# can-transceiver.net
KiCad netlist of a schematic drawn in Altium Designer
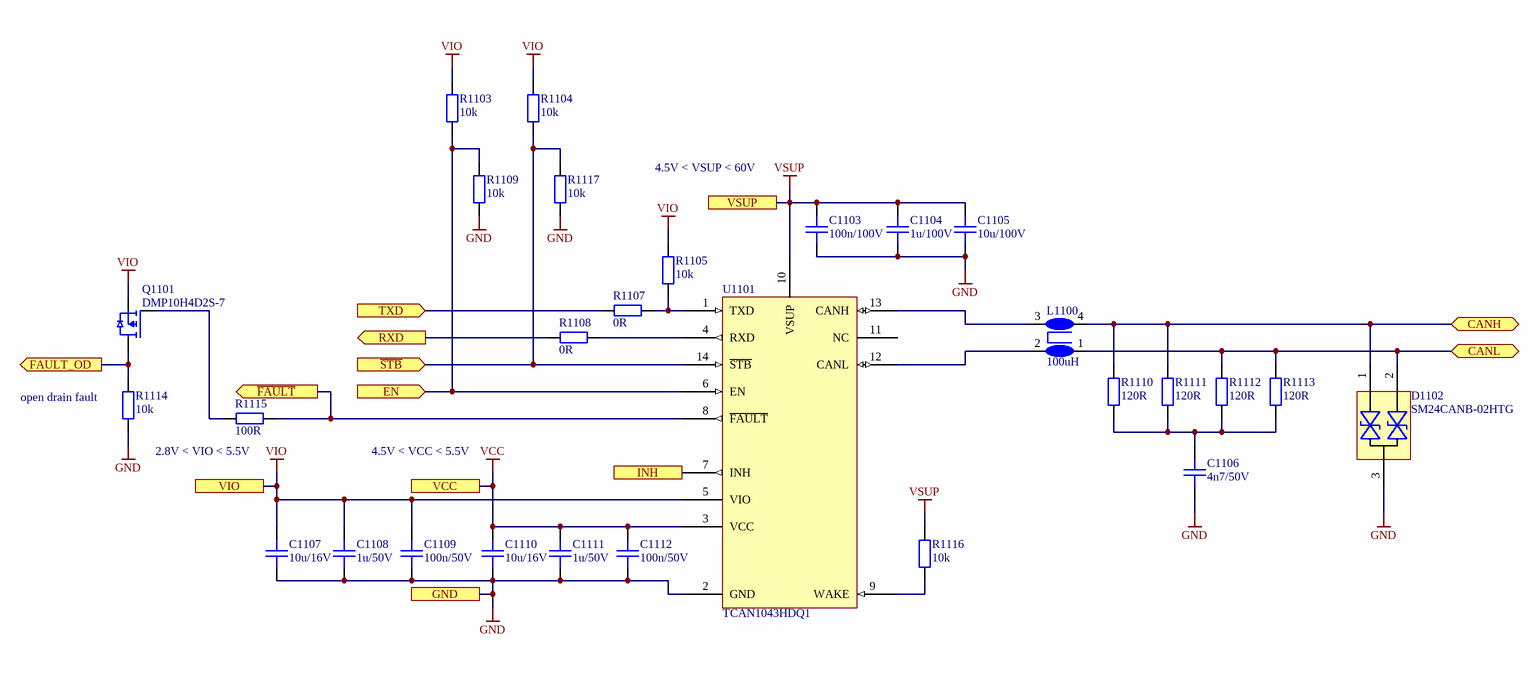
[diagram p0: can-transceiver.SchDoc]

(export (version "E")
  (design (tool "Eeschema 10.0.6"))
  (components
    (comp (ref "C1103")
      (value "100n/100V")
      (footprint "CAPC1608X08N")
      (description "MLCC")
      (fields (field (name "PART NUMBER") "gen_C_ceramic_100n_100V_X7R_0603"))
      (libsource (lib "OE750") (part "C"))
    )
    (comp (ref "C1104")
      (value "1u/100V")
      (footprint "CAPC3216X18N")
      (description "MLCC")
      (fields (field (name "PART NUMBER") "gen_C_ceramic_1u_100V_X7R_1206"))
      (libsource (lib "OE750") (part "C"))
    )
    (comp (ref "C1105")
      (value "10u/100V")
      (footprint "CAPC5750X28N")
      (description "MLCC")
      (fields (field (name "PART NUMBER") "gen_C_ceramic_10u_100V_X7S_2220"))
      (libsource (lib "OE750") (part "C"))
    )
    (comp (ref "C1106")
      (value "4n7/50V")
      (footprint "CAPC1005X06N")
      (description "MLCC")
      (fields (field (name "PART NUMBER") "gen_C_ceramic_4n7_50V_X7R_0402"))
      (libsource (lib "OE750") (part "C"))
    )
    (comp (ref "C1107")
      (value "10u/16V")
      (footprint "CAPC2012X14N")
      (description "MLCC")
      (fields (field (name "PART NUMBER") "gen_C_ceramic_10u_16V_X7R_0805"))
      (libsource (lib "OE750") (part "C"))
    )
    (comp (ref "C1108")
      (value "1u/50V")
      (footprint "CAPC1608X08N")
      (description "MLCC")
      (fields (field (name "PART NUMBER") "gen_C_ceramic_1u_50V_X7R_0603") (field (name "TOLERANCE") "± 10%"))
      (libsource (lib "OE750") (part "C"))
    )
    (comp (ref "C1109")
      (value "100n/50V")
      (footprint "CAPC1005X06N")
      (description "MLCC")
      (fields (field (name "PART NUMBER") "gen_C_ceramic_100n_50V_X7R_0402"))
      (libsource (lib "OE750") (part "C"))
    )
    (comp (ref "C1110")
      (value "10u/16V")
      (footprint "CAPC2012X14N")
      (description "MLCC")
      (fields (field (name "PART NUMBER") "gen_C_ceramic_10u_16V_X7R_0805"))
      (libsource (lib "OE750") (part "C"))
    )
    (comp (ref "C1111")
      (value "1u/50V")
      (footprint "CAPC1608X08N")
      (description "MLCC")
      (fields (field (name "PART NUMBER") "gen_C_ceramic_1u_50V_X7R_0603") (field (name "TOLERANCE") "± 10%"))
      (libsource (lib "OE750") (part "C"))
    )
    (comp (ref "C1112")
      (value "100n/50V")
      (footprint "CAPC1005X06N")
      (description "MLCC")
      (fields (field (name "PART NUMBER") "gen_C_ceramic_100n_50V_X7R_0402"))
      (libsource (lib "OE750") (part "C"))
    )
    (comp (ref "D1102")
      (value "SM24CANB-02HTG")
      (footprint "LF_SOT23-3")
      (description "CAN ESD Protection Diode Array")
      (fields (field (name "MANUFACTURER") "Littelfuse"))
      (libsource (lib "OE750") (part "SM24CANB"))
    )
    (comp (ref "L1100")
      (value "100uH")
      (footprint "MURATA_DLW32SH")
      (description "Common Mode Choke")
      (fields (field (name "PART NUMBER") "DLW32SH101XF2L") (field (name "MANUFACTURER") "Murata"))
      (libsource (lib "OE750") (part "L_CM"))
    )
    (comp (ref "Q1101")
      (value "DMP10H4D2S-7")
      (footprint "SOT95P237X110-3N")
      (description "MOSFET-Transistor, p-Kanal, 0.27 A, 100 V, 4.2 ohm")
      (fields (field (name "MANUFACTURER") "Diodes"))
      (libsource (lib "OE750") (part "PMOS"))
    )
    (comp (ref "R1103")
      (value "10k")
      (footprint "RESC1005X04N")
      (description "SMD Resistor 10k 0402")
      (fields (field (name "PART NUMBER") "gen_R_10k_0402") (field (name "TOLERANCE") "1%"))
      (libsource (lib "OE750") (part "R"))
    )
    (comp (ref "R1104")
      (value "10k")
      (footprint "RESC1005X04N")
      (description "SMD Resistor 10k 0402")
      (fields (field (name "PART NUMBER") "gen_R_10k_0402") (field (name "TOLERANCE") "1%"))
      (libsource (lib "OE750") (part "R"))
    )
    (comp (ref "R1105")
      (value "10k")
      (footprint "RESC1005X04N")
      (description "SMD Resistor 10k 0402")
      (fields (field (name "PART NUMBER") "gen_R_10k_0402") (field (name "TOLERANCE") "1%"))
      (libsource (lib "OE750") (part "R"))
    )
    (comp (ref "R1107")
      (value "0R")
      (footprint "RESC1005X04N")
      (description "SMD Resistor 0R 0402")
      (fields (field (name "PART NUMBER") "gen_R_0R_0402") (field (name "POWER") "0.063W"))
      (libsource (lib "OE750") (part "R"))
    )
    (comp (ref "R1108")
      (value "0R")
      (footprint "RESC1005X04N")
      (description "SMD Resistor 0R 0402")
      (fields (field (name "PART NUMBER") "gen_R_0R_0402") (field (name "POWER") "0.063W"))
      (libsource (lib "OE750") (part "R"))
    )
    (comp (ref "R1109")
      (value "10k")
      (footprint "RESC1005X04N")
      (description "SMD Resistor 10k 0402")
      (fields (field (name "PART NUMBER") "gen_R_10k_0402") (field (name "TOLERANCE") "1%"))
      (libsource (lib "OE750") (part "R"))
    )
    (comp (ref "R1110")
      (value "120R")
      (footprint "RESC3216X06N")
      (description "SMD Resistor 120R 1206")
      (fields (field (name "PART NUMBER") "gen_R_120R_1206") (field (name "TOLERANCE") "1%"))
      (libsource (lib "OE750") (part "R"))
    )
    (comp (ref "R1111")
      (value "120R")
      (footprint "RESC3216X06N")
      (description "SMD Resistor 120R 1206")
      (fields (field (name "PART NUMBER") "gen_R_120R_1206") (field (name "TOLERANCE") "1%"))
      (libsource (lib "OE750") (part "R"))
    )
    (comp (ref "R1112")
      (value "120R")
      (footprint "RESC3216X06N")
      (description "SMD Resistor 120R 1206")
      (fields (field (name "PART NUMBER") "gen_R_120R_1206") (field (name "TOLERANCE") "1%"))
      (libsource (lib "OE750") (part "R"))
    )
    (comp (ref "R1113")
      (value "120R")
      (footprint "RESC3216X06N")
      (description "SMD Resistor 120R 1206")
      (fields (field (name "PART NUMBER") "gen_R_120R_1206") (field (name "TOLERANCE") "1%"))
      (libsource (lib "OE750") (part "R"))
    )
    (comp (ref "R1114")
      (value "10k")
      (footprint "RESC1005X04N")
      (description "SMD Resistor 10k 0402")
      (fields (field (name "PART NUMBER") "gen_R_10k_0402") (field (name "TOLERANCE") "1%"))
      (libsource (lib "OE750") (part "R"))
    )
    (comp (ref "R1115")
      (value "100R")
      (footprint "RESC1005X04N")
      (description "SMD Resistor 100R 0402")
      (fields (field (name "PART NUMBER") "gen_R_100R_0402") (field (name "TOLERANCE") "1%"))
      (libsource (lib "OE750") (part "R"))
    )
    (comp (ref "R1116")
      (value "10k")
      (footprint "RESC1005X04N")
      (description "SMD Resistor 10k 0402")
      (fields (field (name "PART NUMBER") "gen_R_10k_0402") (field (name "TOLERANCE") "1%"))
      (libsource (lib "OE750") (part "R"))
    )
    (comp (ref "R1117")
      (value "10k")
      (footprint "RESC1005X04N")
      (description "SMD Resistor 10k 0402")
      (fields (field (name "PART NUMBER") "gen_R_10k_0402") (field (name "TOLERANCE") "1%"))
      (libsource (lib "OE750") (part "R"))
    )
    (comp (ref "U1101")
      (value "TCAN1043HDQ1")
      (footprint "TI_D0014A-C01_SOIC-14")
      (description "Low-Power Fault Protected CAN Transceiver with CAN FD and Wake")
      (fields (field (name "MANUFACTURER") "Texas Instruments"))
      (libsource (lib "OE750") (part "TCAN1043_SOIC14"))
    )
  )
  (nets
    (net (code "1") (name "/CANH") (class "Default")
      (node (ref "D1102") (pin "1") (pintype "passive"))
      (node (ref "L1100") (pin "4") (pinfunction "4_4") (pintype "passive"))
      (node (ref "R1110") (pin "2") (pinfunction "2_2") (pintype "passive"))
      (node (ref "R1111") (pin "2") (pinfunction "2_2") (pintype "passive"))
    )
    (net (code "2") (name "/CANL") (class "Default")
      (node (ref "D1102") (pin "2") (pintype "passive"))
      (node (ref "L1100") (pin "1") (pinfunction "1_1") (pintype "passive"))
      (node (ref "R1112") (pin "2") (pinfunction "2_2") (pintype "passive"))
      (node (ref "R1113") (pin "2") (pinfunction "2_2") (pintype "passive"))
    )
    (net (code "3") (name "/EN") (class "Default")
      (node (ref "R1103") (pin "1") (pinfunction "1_1") (pintype "passive"))
      (node (ref "R1109") (pin "2") (pinfunction "2_2") (pintype "passive"))
      (node (ref "U1101") (pin "6") (pinfunction "EN_6") (pintype "input"))
    )
    (net (code "4") (name "/FAULT") (class "Default")
      (node (ref "R1115") (pin "2") (pinfunction "2_2") (pintype "passive"))
      (node (ref "U1101") (pin "8") (pinfunction "FAULT_8") (pintype "output"))
    )
    (net (code "5") (name "/FAULT_OD") (class "Default")
      (node (ref "Q1101") (pin "D") (pinfunction "D_D") (pintype "passive"))
      (node (ref "R1114") (pin "2") (pinfunction "2_2") (pintype "passive"))
    )
    (net (code "6") (name "/INH") (class "Default")
      (node (ref "U1101") (pin "7") (pinfunction "INH_7") (pintype "output"))
    )
    (net (code "7") (name "/RXD") (class "Default")
      (node (ref "R1108") (pin "1") (pinfunction "1_1") (pintype "passive"))
    )
    (net (code "8") (name "/STB") (class "Default")
      (node (ref "R1104") (pin "1") (pinfunction "1_1") (pintype "passive"))
      (node (ref "R1117") (pin "2") (pinfunction "2_2") (pintype "passive"))
      (node (ref "U1101") (pin "14") (pinfunction "STB_14") (pintype "input"))
    )
    (net (code "9") (name "/TXD") (class "Default")
      (node (ref "R1107") (pin "1") (pinfunction "1_1") (pintype "passive"))
    )
    (net (code "10") (name "GND") (class "Default")
      (node (ref "C1103") (pin "1") (pinfunction "1_1") (pintype "passive"))
      (node (ref "C1104") (pin "1") (pinfunction "1_1") (pintype "passive"))
      (node (ref "C1105") (pin "1") (pinfunction "1_1") (pintype "passive"))
      (node (ref "C1106") (pin "1") (pinfunction "1_1") (pintype "passive"))
      (node (ref "C1107") (pin "1") (pinfunction "1_1") (pintype "passive"))
      (node (ref "C1108") (pin "1") (pinfunction "1_1") (pintype "passive"))
      (node (ref "C1109") (pin "1") (pinfunction "1_1") (pintype "passive"))
      (node (ref "C1110") (pin "1") (pinfunction "1_1") (pintype "passive"))
      (node (ref "C1111") (pin "1") (pinfunction "1_1") (pintype "passive"))
      (node (ref "C1112") (pin "1") (pinfunction "1_1") (pintype "passive"))
      (node (ref "D1102") (pin "3") (pintype "power_in"))
      (node (ref "R1109") (pin "1") (pinfunction "1_1") (pintype "passive"))
      (node (ref "R1114") (pin "1") (pinfunction "1_1") (pintype "passive"))
      (node (ref "R1117") (pin "1") (pinfunction "1_1") (pintype "passive"))
      (node (ref "U1101") (pin "2") (pinfunction "GND_2") (pintype "power_in"))
    )
    (net (code "11") (name "Net-(C1106-Pad2)") (class "Default")
      (node (ref "C1106") (pin "2") (pinfunction "2_2") (pintype "passive"))
      (node (ref "R1110") (pin "1") (pinfunction "1_1") (pintype "passive"))
      (node (ref "R1111") (pin "1") (pinfunction "1_1") (pintype "passive"))
      (node (ref "R1112") (pin "1") (pinfunction "1_1") (pintype "passive"))
      (node (ref "R1113") (pin "1") (pinfunction "1_1") (pintype "passive"))
    )
    (net (code "12") (name "Net-(Q1101-PadG)") (class "Default")
      (node (ref "Q1101") (pin "G") (pinfunction "G_G") (pintype "passive"))
      (node (ref "R1115") (pin "1") (pinfunction "1_1") (pintype "passive"))
    )
    (net (code "13") (name "Net-(U1101-CANH)") (class "Default")
      (node (ref "L1100") (pin "3") (pinfunction "3_3") (pintype "passive"))
      (node (ref "U1101") (pin "13") (pinfunction "CANH_13") (pintype "bidirectional"))
    )
    (net (code "14") (name "Net-(U1101-CANL)") (class "Default")
      (node (ref "L1100") (pin "2") (pinfunction "2_2") (pintype "passive"))
      (node (ref "U1101") (pin "12") (pinfunction "CANL_12") (pintype "bidirectional"))
    )
    (net (code "15") (name "Net-(U1101-RXD)") (class "Default")
      (node (ref "R1108") (pin "2") (pinfunction "2_2") (pintype "passive"))
      (node (ref "U1101") (pin "4") (pinfunction "RXD_4") (pintype "output"))
    )
    (net (code "16") (name "Net-(U1101-TXD)") (class "Default")
      (node (ref "R1105") (pin "1") (pinfunction "1_1") (pintype "passive"))
      (node (ref "R1107") (pin "2") (pinfunction "2_2") (pintype "passive"))
      (node (ref "U1101") (pin "1") (pinfunction "TXD_1") (pintype "input"))
    )
    (net (code "17") (name "Net-(U1101-WAKE)") (class "Default")
      (node (ref "R1116") (pin "1") (pinfunction "1_1") (pintype "passive"))
      (node (ref "U1101") (pin "9") (pinfunction "WAKE_9") (pintype "input"))
    )
    (net (code "18") (name "VCC") (class "Default")
      (node (ref "C1110") (pin "2") (pinfunction "2_2") (pintype "passive"))
      (node (ref "C1111") (pin "2") (pinfunction "2_2") (pintype "passive"))
      (node (ref "C1112") (pin "2") (pinfunction "2_2") (pintype "passive"))
      (node (ref "U1101") (pin "3") (pinfunction "VCC_3") (pintype "power_in"))
    )
    (net (code "19") (name "VIO") (class "Default")
      (node (ref "C1107") (pin "2") (pinfunction "2_2") (pintype "passive"))
      (node (ref "C1108") (pin "2") (pinfunction "2_2") (pintype "passive"))
      (node (ref "C1109") (pin "2") (pinfunction "2_2") (pintype "passive"))
      (node (ref "Q1101") (pin "S") (pinfunction "S_S") (pintype "passive"))
      (node (ref "R1103") (pin "2") (pinfunction "2_2") (pintype "passive"))
      (node (ref "R1104") (pin "2") (pinfunction "2_2") (pintype "passive"))
      (node (ref "R1105") (pin "2") (pinfunction "2_2") (pintype "passive"))
      (node (ref "U1101") (pin "5") (pinfunction "VIO_5") (pintype "power_in"))
    )
    (net (code "20") (name "VSUP") (class "Default")
      (node (ref "C1103") (pin "2") (pinfunction "2_2") (pintype "passive"))
      (node (ref "C1104") (pin "2") (pinfunction "2_2") (pintype "passive"))
      (node (ref "C1105") (pin "2") (pinfunction "2_2") (pintype "passive"))
      (node (ref "R1116") (pin "2") (pinfunction "2_2") (pintype "passive"))
      (node (ref "U1101") (pin "10") (pinfunction "VSUP_10") (pintype "power_in"))
    )
    (net (code "21") (name "unconnected-(U1101-NC-Pad11)") (class "Default")
      (node (ref "U1101") (pin "11") (pinfunction "NC_11") (pintype "passive"))
    )
  )
)
